# indicator_assembly.net
KiCad netlist of a schematic drawn in EAGLE
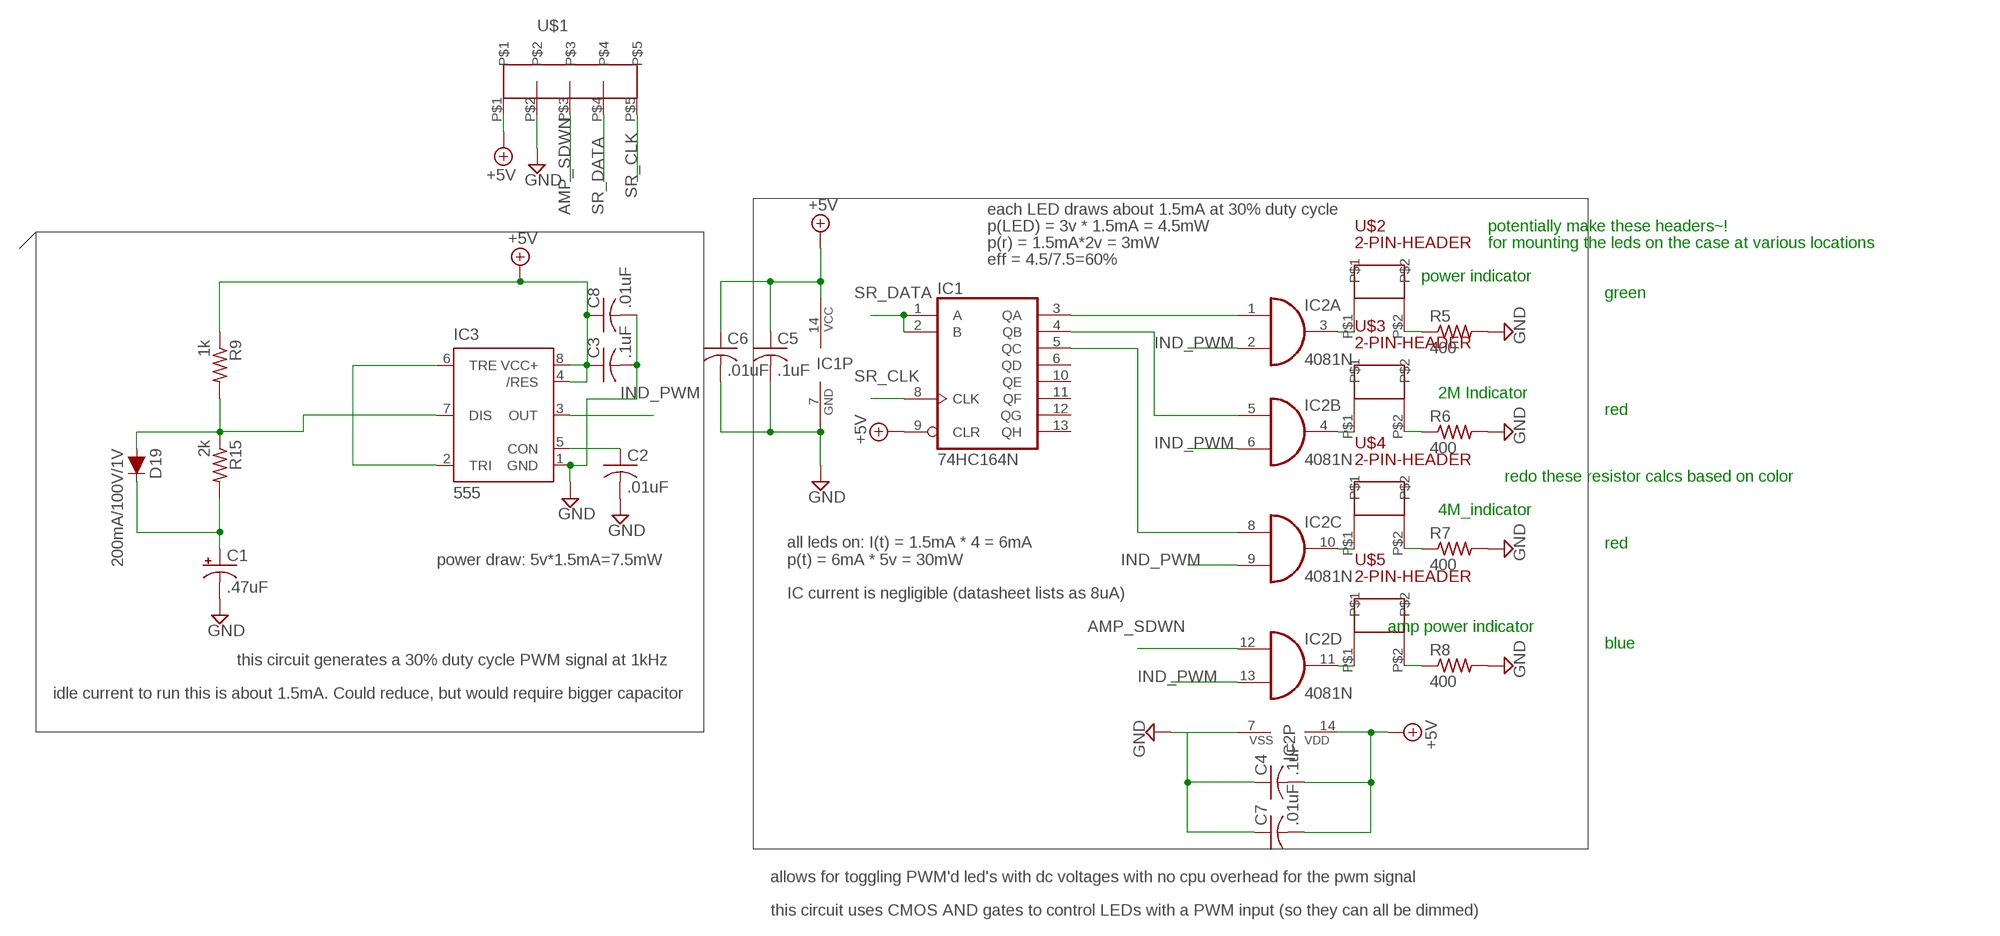
[diagram p0: schematic, sheet 1]

(export (version "E")
  (design (tool "Eeschema 10.0.6"))
  (components
    (comp (ref "C1")
      (value ".47uF")
      (footprint "eagle-import:E2-4")
      (libsource (lib "eagle-import") (part "CPOL-USE2-4"))
    )
    (comp (ref "C2")
      (value ".01uF")
      (footprint "eagle-import:C025-030X050")
      (libsource (lib "eagle-import") (part "C-US025-030X050"))
    )
    (comp (ref "C3")
      (value ".1uF")
      (footprint "eagle-import:C025-030X050")
      (libsource (lib "eagle-import") (part "C-US025-030X050"))
    )
    (comp (ref "C4")
      (value ".1uF")
      (footprint "eagle-import:C025-030X050")
      (libsource (lib "eagle-import") (part "C-US025-030X050"))
    )
    (comp (ref "C5")
      (value ".1uF")
      (footprint "eagle-import:C025-030X050")
      (libsource (lib "eagle-import") (part "C-US025-030X050"))
    )
    (comp (ref "C6")
      (value ".01uF")
      (footprint "eagle-import:C025-030X050")
      (libsource (lib "eagle-import") (part "C-US025-030X050"))
    )
    (comp (ref "C7")
      (value ".01uF")
      (footprint "eagle-import:C025-030X050")
      (libsource (lib "eagle-import") (part "C-US025-030X050"))
    )
    (comp (ref "C8")
      (value ".01uF")
      (footprint "eagle-import:C025-030X050")
      (libsource (lib "eagle-import") (part "C-US025-030X050"))
    )
    (comp (ref "D19")
      (value "200mA/100V/1V")
      (footprint "eagle-import:DIODE-1N4148")
      (libsource (lib "eagle-import") (part "DIODE-1N4148"))
    )
    (comp (ref "IC1")
      (value "74HC164N")
      (footprint "eagle-import:DIL14")
      (libsource (lib "eagle-import") (part "74164NHC"))
    )
    (comp (ref "IC2")
      (value "4081N")
      (footprint "eagle-import:DIL14")
      (libsource (lib "eagle-import") (part "4081N"))
    )
    (comp (ref "IC3")
      (value "555")
      (footprint "eagle-import:DIP08")
      (libsource (lib "eagle-import") (part "555P"))
    )
    (comp (ref "R5")
      (value "400")
      (footprint "eagle-import:0204_7")
      (libsource (lib "eagle-import") (part "R-US_0204/7"))
    )
    (comp (ref "R6")
      (value "400")
      (footprint "eagle-import:0204_7")
      (libsource (lib "eagle-import") (part "R-US_0204/7"))
    )
    (comp (ref "R7")
      (value "400")
      (footprint "eagle-import:0204_7")
      (libsource (lib "eagle-import") (part "R-US_0204/7"))
    )
    (comp (ref "R8")
      (value "400")
      (footprint "eagle-import:0204_7")
      (libsource (lib "eagle-import") (part "R-US_0204/7"))
    )
    (comp (ref "R9")
      (value "1k")
      (footprint "eagle-import:0204_7")
      (libsource (lib "eagle-import") (part "R-US_0204/7"))
    )
    (comp (ref "R15")
      (value "2k")
      (footprint "eagle-import:0204_7")
      (libsource (lib "eagle-import") (part "R-US_0204/7"))
    )
    (comp (ref "U$1")
      (value "5-PIN-HEADER")
      (footprint "eagle-import:5-PIN-HEADER")
      (libsource (lib "eagle-import") (part "5-PIN-HEADER"))
    )
    (comp (ref "U$2")
      (value "2-PIN-HEADER")
      (footprint "eagle-import:2-PIN-HEADER")
      (libsource (lib "eagle-import") (part "2-PIN-HEADER"))
    )
    (comp (ref "U$3")
      (value "2-PIN-HEADER")
      (footprint "eagle-import:2-PIN-HEADER")
      (libsource (lib "eagle-import") (part "2-PIN-HEADER"))
    )
    (comp (ref "U$4")
      (value "2-PIN-HEADER")
      (footprint "eagle-import:2-PIN-HEADER")
      (libsource (lib "eagle-import") (part "2-PIN-HEADER"))
    )
    (comp (ref "U$5")
      (value "2-PIN-HEADER")
      (footprint "eagle-import:2-PIN-HEADER")
      (libsource (lib "eagle-import") (part "2-PIN-HEADER"))
    )
  )
  (nets
    (net (code "1") (name "+5V") (class "Default")
      (node (ref "C3") (pin "1") (pinfunction "1_1") (pintype "passive"))
      (node (ref "C4") (pin "2") (pinfunction "2_2") (pintype "passive"))
      (node (ref "C5") (pin "1") (pinfunction "1_1") (pintype "passive"))
      (node (ref "C6") (pin "1") (pinfunction "1_1") (pintype "passive"))
      (node (ref "C7") (pin "2") (pinfunction "2_2") (pintype "passive"))
      (node (ref "C8") (pin "1") (pinfunction "1_1") (pintype "passive"))
      (node (ref "IC1") (pin "14") (pinfunction "VCC_14") (pintype "power_in"))
      (node (ref "IC1") (pin "9") (pinfunction "CLR_9") (pintype "input"))
      (node (ref "IC2") (pin "14") (pinfunction "VDD_14") (pintype "power_in"))
      (node (ref "IC3") (pin "4") (pinfunction "/RES_4") (pintype "input"))
      (node (ref "IC3") (pin "8") (pinfunction "VCC+_8") (pintype "power_in"))
      (node (ref "R9") (pin "1") (pinfunction "1_1") (pintype "passive"))
      (node (ref "U$1") (pin "P$1") (pinfunction "P$1_P$1") (pintype "bidirectional"))
    )
    (net (code "2") (name "/AMP_SDWN") (class "Default")
      (node (ref "IC2") (pin "12") (pinfunction "I0_12") (pintype "input"))
      (node (ref "U$1") (pin "P$3") (pinfunction "P$3_P$3") (pintype "bidirectional"))
    )
    (net (code "3") (name "/IND_PWM") (class "Default")
      (node (ref "IC2") (pin "13") (pinfunction "I1_13") (pintype "input"))
      (node (ref "IC2") (pin "2") (pinfunction "I1_2") (pintype "input"))
      (node (ref "IC2") (pin "6") (pinfunction "I1_6") (pintype "input"))
      (node (ref "IC2") (pin "9") (pinfunction "I1_9") (pintype "input"))
      (node (ref "IC3") (pin "3") (pinfunction "OUT_3") (pintype "output"))
    )
    (net (code "4") (name "/SR_CLK") (class "Default")
      (node (ref "IC1") (pin "8") (pinfunction "CLK_8") (pintype "input"))
      (node (ref "U$1") (pin "P$5") (pinfunction "P$5_P$5") (pintype "bidirectional"))
    )
    (net (code "5") (name "/SR_DATA") (class "Default")
      (node (ref "IC1") (pin "1") (pinfunction "A_1") (pintype "input"))
      (node (ref "IC1") (pin "2") (pinfunction "B_2") (pintype "input"))
      (node (ref "U$1") (pin "P$4") (pinfunction "P$4_P$4") (pintype "bidirectional"))
    )
    (net (code "6") (name "GND") (class "Default")
      (node (ref "C1") (pin "-") (pinfunction "-_-") (pintype "passive"))
      (node (ref "C2") (pin "2") (pinfunction "2_2") (pintype "passive"))
      (node (ref "C3") (pin "2") (pinfunction "2_2") (pintype "passive"))
      (node (ref "C4") (pin "1") (pinfunction "1_1") (pintype "passive"))
      (node (ref "C5") (pin "2") (pinfunction "2_2") (pintype "passive"))
      (node (ref "C6") (pin "2") (pinfunction "2_2") (pintype "passive"))
      (node (ref "C7") (pin "1") (pinfunction "1_1") (pintype "passive"))
      (node (ref "C8") (pin "2") (pinfunction "2_2") (pintype "passive"))
      (node (ref "IC1") (pin "7") (pinfunction "GND_7") (pintype "power_in"))
      (node (ref "IC2") (pin "7") (pinfunction "VSS_7") (pintype "power_in"))
      (node (ref "IC3") (pin "1") (pinfunction "GND_1") (pintype "power_in"))
      (node (ref "R5") (pin "2") (pinfunction "2_2") (pintype "passive"))
      (node (ref "R6") (pin "2") (pinfunction "2_2") (pintype "passive"))
      (node (ref "R7") (pin "2") (pinfunction "2_2") (pintype "passive"))
      (node (ref "R8") (pin "2") (pinfunction "2_2") (pintype "passive"))
      (node (ref "U$1") (pin "P$2") (pinfunction "P$2_P$2") (pintype "bidirectional"))
    )
    (net (code "7") (name "Net-(C1-Pad+)") (class "Default")
      (node (ref "C1") (pin "+") (pinfunction "+_+") (pintype "passive"))
      (node (ref "D19") (pin "C") (pinfunction "C_C") (pintype "passive"))
      (node (ref "R15") (pin "2") (pinfunction "2_2") (pintype "passive"))
    )
    (net (code "8") (name "Net-(IC1A-QA)") (class "Default")
      (node (ref "IC1") (pin "3") (pinfunction "QA_3") (pintype "output"))
      (node (ref "IC2") (pin "1") (pinfunction "I0_1") (pintype "input"))
    )
    (net (code "9") (name "Net-(IC1A-QB)") (class "Default")
      (node (ref "IC1") (pin "4") (pinfunction "QB_4") (pintype "output"))
      (node (ref "IC2") (pin "5") (pinfunction "I0_5") (pintype "input"))
    )
    (net (code "10") (name "Net-(IC1A-QC)") (class "Default")
      (node (ref "IC1") (pin "5") (pinfunction "QC_5") (pintype "output"))
      (node (ref "IC2") (pin "8") (pinfunction "I0_8") (pintype "input"))
    )
    (net (code "11") (name "Net-(IC2A-O)") (class "Default")
      (node (ref "IC2") (pin "3") (pinfunction "O_3") (pintype "output"))
      (node (ref "U$2") (pin "P$1") (pinfunction "P$1_P$1") (pintype "bidirectional"))
    )
    (net (code "12") (name "Net-(IC2B-O)") (class "Default")
      (node (ref "IC2") (pin "4") (pinfunction "O_4") (pintype "output"))
      (node (ref "U$3") (pin "P$1") (pinfunction "P$1_P$1") (pintype "bidirectional"))
    )
    (net (code "13") (name "Net-(IC2C-O)") (class "Default")
      (node (ref "IC2") (pin "10") (pinfunction "O_10") (pintype "output"))
      (node (ref "U$4") (pin "P$1") (pinfunction "P$1_P$1") (pintype "bidirectional"))
    )
    (net (code "14") (name "Net-(IC2D-O)") (class "Default")
      (node (ref "IC2") (pin "11") (pinfunction "O_11") (pintype "output"))
      (node (ref "U$5") (pin "P$1") (pinfunction "P$1_P$1") (pintype "bidirectional"))
    )
    (net (code "15") (name "Net-(IC3-CON)") (class "Default")
      (node (ref "C2") (pin "1") (pinfunction "1_1") (pintype "passive"))
      (node (ref "IC3") (pin "5") (pinfunction "CON_5") (pintype "input"))
    )
    (net (code "16") (name "Net-(IC3-DIS)") (class "Default")
      (node (ref "D19") (pin "A") (pinfunction "A_A") (pintype "passive"))
      (node (ref "IC3") (pin "7") (pinfunction "DIS_7") (pintype "input"))
      (node (ref "R15") (pin "1") (pinfunction "1_1") (pintype "passive"))
      (node (ref "R9") (pin "2") (pinfunction "2_2") (pintype "passive"))
    )
    (net (code "17") (name "Net-(IC3-TRE)") (class "Default")
      (node (ref "IC3") (pin "2") (pinfunction "TRI_2") (pintype "input"))
      (node (ref "IC3") (pin "6") (pinfunction "TRE_6") (pintype "input"))
    )
    (net (code "18") (name "Net-(R5-Pad1)") (class "Default")
      (node (ref "R5") (pin "1") (pinfunction "1_1") (pintype "passive"))
      (node (ref "U$2") (pin "P$2") (pinfunction "P$2_P$2") (pintype "bidirectional"))
    )
    (net (code "19") (name "Net-(R6-Pad1)") (class "Default")
      (node (ref "R6") (pin "1") (pinfunction "1_1") (pintype "passive"))
      (node (ref "U$3") (pin "P$2") (pinfunction "P$2_P$2") (pintype "bidirectional"))
    )
    (net (code "20") (name "Net-(R7-Pad1)") (class "Default")
      (node (ref "R7") (pin "1") (pinfunction "1_1") (pintype "passive"))
      (node (ref "U$4") (pin "P$2") (pinfunction "P$2_P$2") (pintype "bidirectional"))
    )
    (net (code "21") (name "Net-(R8-Pad1)") (class "Default")
      (node (ref "R8") (pin "1") (pinfunction "1_1") (pintype "passive"))
      (node (ref "U$5") (pin "P$2") (pinfunction "P$2_P$2") (pintype "bidirectional"))
    )
    (net (code "22") (name "unconnected-(IC1A-QD-Pad6)") (class "Default")
      (node (ref "IC1") (pin "6") (pinfunction "QD_6") (pintype "output"))
    )
    (net (code "23") (name "unconnected-(IC1A-QE-Pad10)") (class "Default")
      (node (ref "IC1") (pin "10") (pinfunction "QE_10") (pintype "output"))
    )
    (net (code "24") (name "unconnected-(IC1A-QF-Pad11)") (class "Default")
      (node (ref "IC1") (pin "11") (pinfunction "QF_11") (pintype "output"))
    )
    (net (code "25") (name "unconnected-(IC1A-QG-Pad12)") (class "Default")
      (node (ref "IC1") (pin "12") (pinfunction "QG_12") (pintype "output"))
    )
    (net (code "26") (name "unconnected-(IC1A-QH-Pad13)") (class "Default")
      (node (ref "IC1") (pin "13") (pinfunction "QH_13") (pintype "output"))
    )
  )
)
